# MCU.net
KiCad netlist of a schematic drawn in Altium Designer
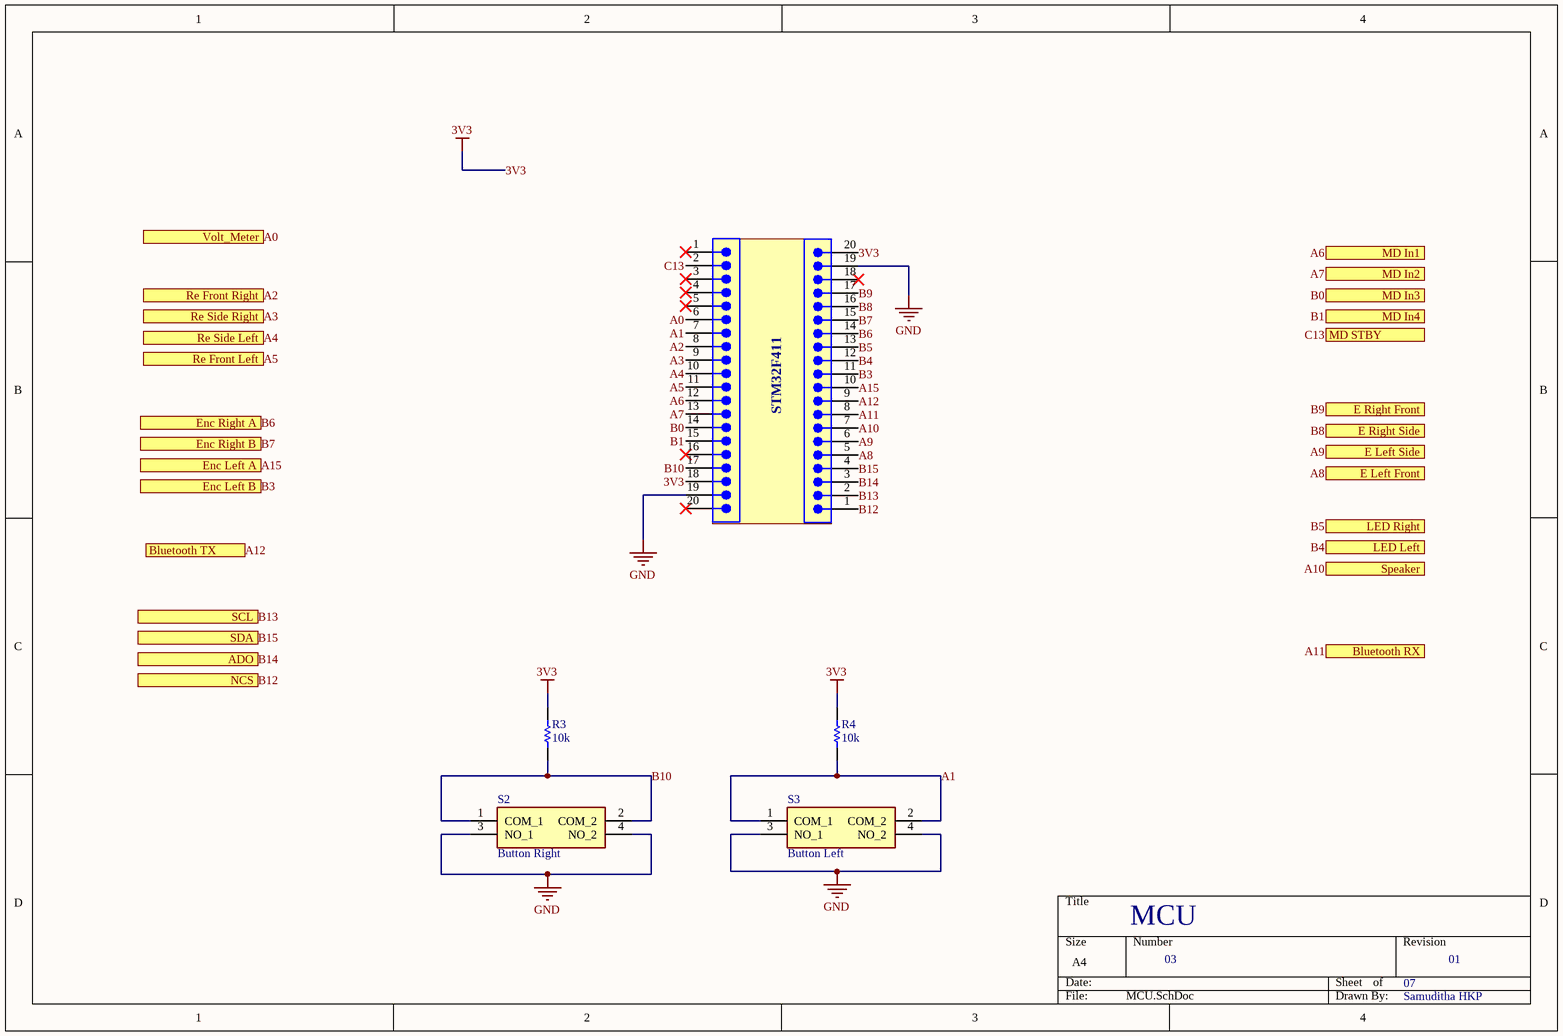
[diagram p0: MCU.SchDoc]

(export (version "E")
  (design (tool "Eeschema 10.0.6"))
  (components
    (comp (ref "P4")
      (value "61302011121")
      (footprint "61302011121")
      (libsource (lib "Altium Content Vault") (part "Header_Male_1R_20P"))
    )
    (comp (ref "P5")
      (value "61302011121")
      (footprint "61302011121")
      (libsource (lib "Altium Content Vault") (part "Header_Male_1R_20P"))
    )
    (comp (ref "R3")
      (value "10k")
      (footprint "RESC1005X40X25LL05T10")
      (fields (field (name "PART NUMBER") "RC0402FR-0710KL") (field (name "MANUFACTURER") "Yageo / Phycomp"))
      (libsource (lib "Altium Content Vault") (part "RES"))
    )
    (comp (ref "R4")
      (value "10k")
      (footprint "RESC1005X40X25LL05T10")
      (fields (field (name "PART NUMBER") "RC0402FR-0710KL") (field (name "MANUFACTURER") "Yageo / Phycomp"))
      (libsource (lib "Altium Content Vault") (part "RES"))
    )
    (comp (ref "S2")
      (value "Button Right")
      (footprint "SamacSys:COM08720")
      (description "Switch")
      (fields
        (field (name "MANUFACTURER_PART_NUMBER") "COM-08720")
        (field (name "MOUSER PART NUMBER") "474-COM-08720")
      )
      (libsource (lib "*") (part "COM-08720"))
    )
    (comp (ref "S3")
      (value "Button Left")
      (footprint "SamacSys:COM08720")
      (description "Switch")
      (fields
        (field (name "MANUFACTURER_PART_NUMBER") "COM-08720")
        (field (name "MOUSER PART NUMBER") "474-COM-08720")
      )
      (libsource (lib "*") (part "COM-08720"))
    )
  )
  (nets
    (net (code "1") (name "/A0") (class "Default")
      (node (ref "P4") (pin "6") (pinfunction "6_6") (pintype "passive"))
    )
    (net (code "2") (name "/A1") (class "Default")
      (node (ref "P4") (pin "7") (pinfunction "7_7") (pintype "passive"))
      (node (ref "R4") (pin "1") (pinfunction "1_1") (pintype "passive"))
      (node (ref "S3") (pin "1") (pinfunction "COM_1_1") (pintype "passive"))
      (node (ref "S3") (pin "2") (pinfunction "COM_2_2") (pintype "passive"))
    )
    (net (code "3") (name "/A2") (class "Default")
      (node (ref "P4") (pin "8") (pinfunction "8_8") (pintype "passive"))
    )
    (net (code "4") (name "/A3") (class "Default")
      (node (ref "P4") (pin "9") (pinfunction "9_9") (pintype "passive"))
    )
    (net (code "5") (name "/A4") (class "Default")
      (node (ref "P4") (pin "10") (pinfunction "10_10") (pintype "passive"))
    )
    (net (code "6") (name "/A5") (class "Default")
      (node (ref "P4") (pin "11") (pinfunction "11_11") (pintype "passive"))
    )
    (net (code "7") (name "/A6") (class "Default")
      (node (ref "P4") (pin "12") (pinfunction "12_12") (pintype "passive"))
    )
    (net (code "8") (name "/A7") (class "Default")
      (node (ref "P4") (pin "13") (pinfunction "13_13") (pintype "passive"))
    )
    (net (code "9") (name "/A8") (class "Default")
      (node (ref "P5") (pin "5") (pinfunction "5_5") (pintype "passive"))
    )
    (net (code "10") (name "/A9") (class "Default")
      (node (ref "P5") (pin "6") (pinfunction "6_6") (pintype "passive"))
    )
    (net (code "11") (name "/A10") (class "Default")
      (node (ref "P5") (pin "7") (pinfunction "7_7") (pintype "passive"))
    )
    (net (code "12") (name "/A11") (class "Default")
      (node (ref "P5") (pin "8") (pinfunction "8_8") (pintype "passive"))
    )
    (net (code "13") (name "/A12") (class "Default")
      (node (ref "P5") (pin "9") (pinfunction "9_9") (pintype "passive"))
    )
    (net (code "14") (name "/A15") (class "Default")
      (node (ref "P5") (pin "10") (pinfunction "10_10") (pintype "passive"))
    )
    (net (code "15") (name "/B0") (class "Default")
      (node (ref "P4") (pin "14") (pinfunction "14_14") (pintype "passive"))
    )
    (net (code "16") (name "/B1") (class "Default")
      (node (ref "P4") (pin "15") (pinfunction "15_15") (pintype "passive"))
    )
    (net (code "17") (name "/B3") (class "Default")
      (node (ref "P5") (pin "11") (pinfunction "11_11") (pintype "passive"))
    )
    (net (code "18") (name "/B4") (class "Default")
      (node (ref "P5") (pin "12") (pinfunction "12_12") (pintype "passive"))
    )
    (net (code "19") (name "/B5") (class "Default")
      (node (ref "P5") (pin "13") (pinfunction "13_13") (pintype "passive"))
    )
    (net (code "20") (name "/B6") (class "Default")
      (node (ref "P5") (pin "14") (pinfunction "14_14") (pintype "passive"))
    )
    (net (code "21") (name "/B7") (class "Default")
      (node (ref "P5") (pin "15") (pinfunction "15_15") (pintype "passive"))
    )
    (net (code "22") (name "/B8") (class "Default")
      (node (ref "P5") (pin "16") (pinfunction "16_16") (pintype "passive"))
    )
    (net (code "23") (name "/B9") (class "Default")
      (node (ref "P5") (pin "17") (pinfunction "17_17") (pintype "passive"))
    )
    (net (code "24") (name "/B10") (class "Default")
      (node (ref "P4") (pin "17") (pinfunction "17_17") (pintype "passive"))
      (node (ref "R3") (pin "1") (pinfunction "1_1") (pintype "passive"))
      (node (ref "S2") (pin "1") (pinfunction "COM_1_1") (pintype "passive"))
      (node (ref "S2") (pin "2") (pinfunction "COM_2_2") (pintype "passive"))
    )
    (net (code "25") (name "/B12") (class "Default")
      (node (ref "P5") (pin "1") (pinfunction "1_1") (pintype "passive"))
    )
    (net (code "26") (name "/B13") (class "Default")
      (node (ref "P5") (pin "2") (pinfunction "2_2") (pintype "passive"))
    )
    (net (code "27") (name "/B14") (class "Default")
      (node (ref "P5") (pin "3") (pinfunction "3_3") (pintype "passive"))
    )
    (net (code "28") (name "/B15") (class "Default")
      (node (ref "P5") (pin "4") (pinfunction "4_4") (pintype "passive"))
    )
    (net (code "30") (name "/C13") (class "Default")
      (node (ref "P4") (pin "2") (pinfunction "2_2") (pintype "passive"))
    )
    (net (code "43") (name "3V3") (class "Default")
      (node (ref "P4") (pin "18") (pinfunction "18_18") (pintype "passive"))
      (node (ref "P5") (pin "20") (pinfunction "20_20") (pintype "passive"))
      (node (ref "R3") (pin "2") (pinfunction "2_2") (pintype "passive"))
      (node (ref "R4") (pin "2") (pinfunction "2_2") (pintype "passive"))
    )
    (net (code "44") (name "GND") (class "Default")
      (node (ref "P4") (pin "19") (pinfunction "19_19") (pintype "passive"))
      (node (ref "P5") (pin "19") (pinfunction "19_19") (pintype "passive"))
      (node (ref "S2") (pin "3") (pinfunction "NO_1_3") (pintype "passive"))
      (node (ref "S2") (pin "4") (pinfunction "NO_2_4") (pintype "passive"))
      (node (ref "S3") (pin "3") (pinfunction "NO_1_3") (pintype "passive"))
      (node (ref "S3") (pin "4") (pinfunction "NO_2_4") (pintype "passive"))
    )
    (net (code "45") (name "unconnected-(P4-Pad1)") (class "Default")
      (node (ref "P4") (pin "1") (pinfunction "1_1") (pintype "passive+no_connect"))
    )
    (net (code "46") (name "unconnected-(P4-Pad3)") (class "Default")
      (node (ref "P4") (pin "3") (pinfunction "3_3") (pintype "passive+no_connect"))
    )
    (net (code "47") (name "unconnected-(P4-Pad4)") (class "Default")
      (node (ref "P4") (pin "4") (pinfunction "4_4") (pintype "passive+no_connect"))
    )
    (net (code "48") (name "unconnected-(P4-Pad5)") (class "Default")
      (node (ref "P4") (pin "5") (pinfunction "5_5") (pintype "passive+no_connect"))
    )
    (net (code "49") (name "unconnected-(P4-Pad16)") (class "Default")
      (node (ref "P4") (pin "16") (pinfunction "16_16") (pintype "passive+no_connect"))
    )
    (net (code "50") (name "unconnected-(P4-Pad20)") (class "Default")
      (node (ref "P4") (pin "20") (pinfunction "20_20") (pintype "passive+no_connect"))
    )
    (net (code "51") (name "unconnected-(P5-Pad18)") (class "Default")
      (node (ref "P5") (pin "18") (pinfunction "18_18") (pintype "passive+no_connect"))
    )
  )
)
